# switch_board.net
KiCad netlist of a schematic drawn in EAGLE
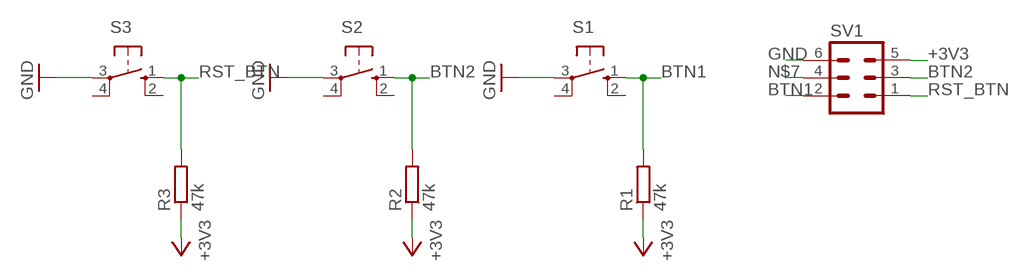
[diagram p0: schematic, sheet 1]

(export (version "E")
  (design (tool "Eeschema 10.0.6"))
  (components
    (comp (ref "R1")
      (value "47k")
      (footprint "eagle-import:0207_10")
      (libsource (lib "eagle-import") (part "R-EU_0207/10"))
    )
    (comp (ref "R2")
      (value "47k")
      (footprint "eagle-import:0207_10")
      (libsource (lib "eagle-import") (part "R-EU_0207/10"))
    )
    (comp (ref "R3")
      (value "47k")
      (footprint "eagle-import:0207_10")
      (libsource (lib "eagle-import") (part "R-EU_0207/10"))
    )
    (comp (ref "S1")
      (value "10-XX")
      (footprint "eagle-import:B3F-10XX")
      (fields (field (name "MPN") "B3F-1000"))
      (libsource (lib "eagle-import") (part "10-XX"))
    )
    (comp (ref "S2")
      (value "10-XX")
      (footprint "eagle-import:B3F-10XX")
      (fields (field (name "MPN") "B3F-1000"))
      (libsource (lib "eagle-import") (part "10-XX"))
    )
    (comp (ref "S3")
      (value "10-XX")
      (footprint "eagle-import:B3F-10XX")
      (fields (field (name "MPN") "B3F-1000"))
      (libsource (lib "eagle-import") (part "10-XX"))
    )
    (comp (ref "SV1")
      (value "ML6")
      (footprint "eagle-import:ML6")
      (libsource (lib "eagle-import") (part "ML6"))
    )
  )
  (nets
    (net (code "1") (name "+3V3") (class "Default")
      (node (ref "R1") (pin "1") (pinfunction "1_1") (pintype "passive"))
      (node (ref "R2") (pin "1") (pinfunction "1_1") (pintype "passive"))
      (node (ref "R3") (pin "1") (pinfunction "1_1") (pintype "passive"))
      (node (ref "SV1") (pin "5") (pinfunction "5_5") (pintype "passive"))
    )
    (net (code "2") (name "/BTN1") (class "Default")
      (node (ref "R1") (pin "2") (pinfunction "2_2") (pintype "passive"))
      (node (ref "S1") (pin "1") (pinfunction "S_1") (pintype "passive"))
      (node (ref "SV1") (pin "2") (pinfunction "2_2") (pintype "passive"))
    )
    (net (code "3") (name "/BTN2") (class "Default")
      (node (ref "R2") (pin "2") (pinfunction "2_2") (pintype "passive"))
      (node (ref "S2") (pin "1") (pinfunction "S_1") (pintype "passive"))
      (node (ref "SV1") (pin "3") (pinfunction "3_3") (pintype "passive"))
    )
    (net (code "4") (name "/N$7") (class "Default")
      (node (ref "SV1") (pin "4") (pinfunction "4_4") (pintype "passive"))
    )
    (net (code "5") (name "/RST_BTN") (class "Default")
      (node (ref "R3") (pin "2") (pinfunction "2_2") (pintype "passive"))
      (node (ref "S3") (pin "1") (pinfunction "S_1") (pintype "passive"))
      (node (ref "SV1") (pin "1") (pinfunction "1_1") (pintype "passive"))
    )
    (net (code "6") (name "GND") (class "Default")
      (node (ref "S1") (pin "3") (pinfunction "P_3") (pintype "passive"))
      (node (ref "S2") (pin "3") (pinfunction "P_3") (pintype "passive"))
      (node (ref "S3") (pin "3") (pinfunction "P_3") (pintype "passive"))
      (node (ref "SV1") (pin "6") (pinfunction "6_6") (pintype "passive"))
    )
    (net (code "7") (name "unconnected-(S1-P1-Pad4)") (class "Default")
      (node (ref "S1") (pin "4") (pinfunction "P1_4") (pintype "passive"))
    )
    (net (code "8") (name "unconnected-(S1-S1-Pad2)") (class "Default")
      (node (ref "S1") (pin "2") (pinfunction "S1_2") (pintype "passive"))
    )
    (net (code "9") (name "unconnected-(S2-P1-Pad4)") (class "Default")
      (node (ref "S2") (pin "4") (pinfunction "P1_4") (pintype "passive"))
    )
    (net (code "10") (name "unconnected-(S2-S1-Pad2)") (class "Default")
      (node (ref "S2") (pin "2") (pinfunction "S1_2") (pintype "passive"))
    )
    (net (code "11") (name "unconnected-(S3-P1-Pad4)") (class "Default")
      (node (ref "S3") (pin "4") (pinfunction "P1_4") (pintype "passive"))
    )
    (net (code "12") (name "unconnected-(S3-S1-Pad2)") (class "Default")
      (node (ref "S3") (pin "2") (pinfunction "S1_2") (pintype "passive"))
    )
  )
)
